# stm32c8t6.net
KiCad netlist of a schematic drawn in Altium Designer
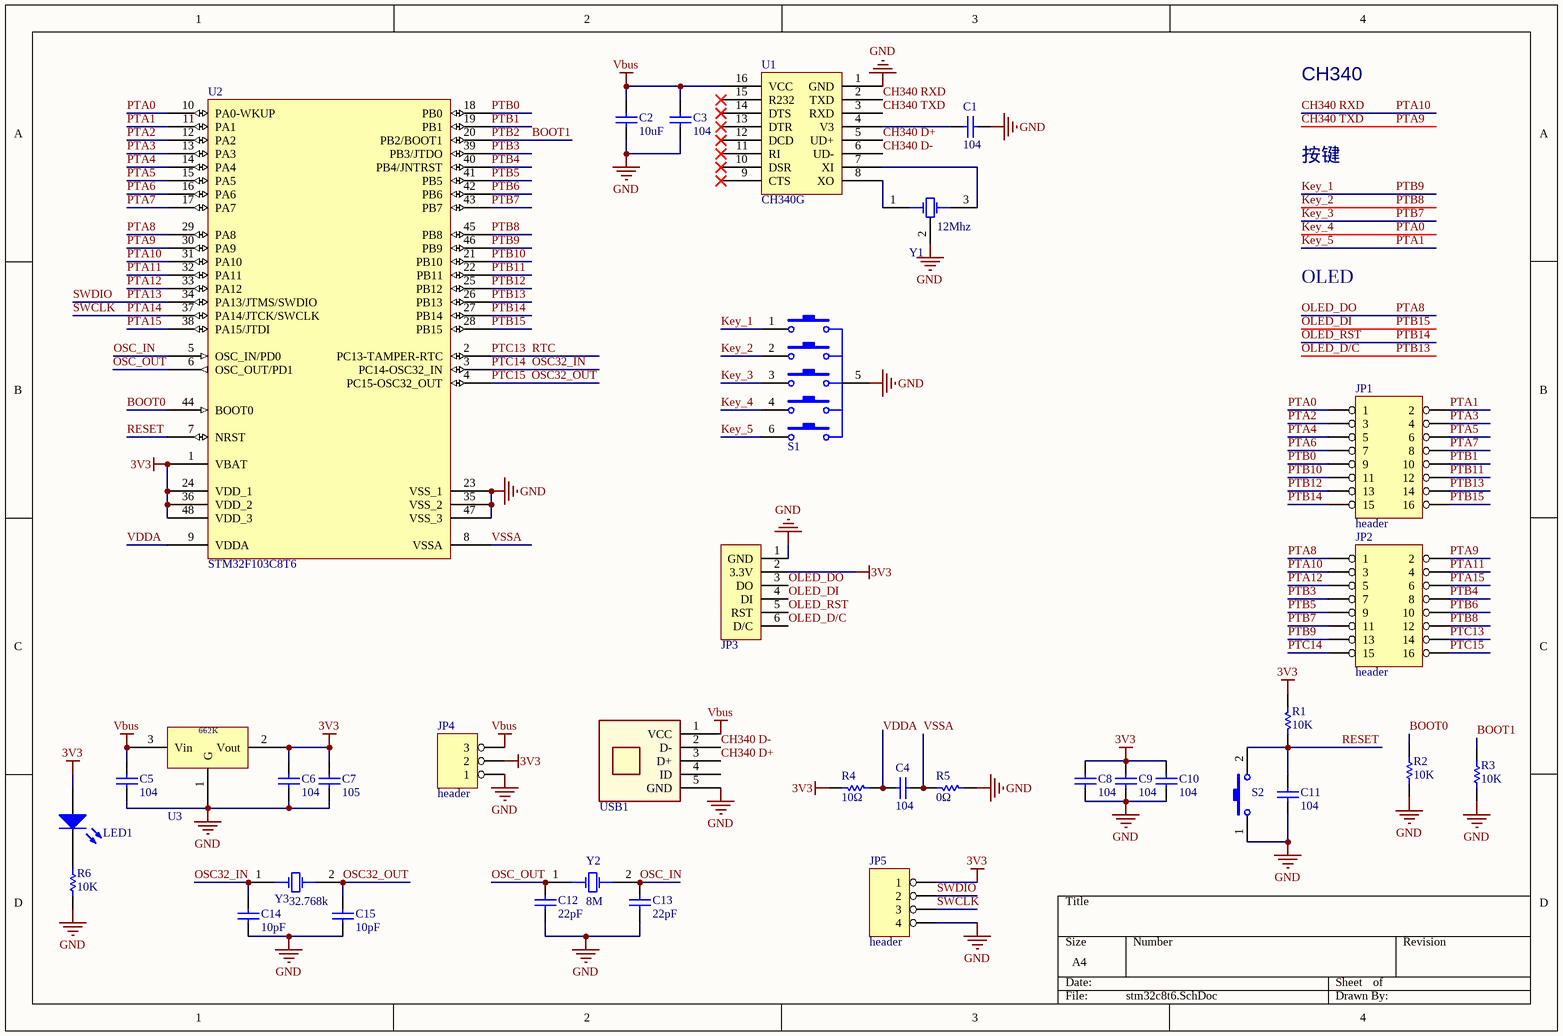
[diagram p0: stm32c8t6.SchDoc]

(export (version "E")
  (design (tool "Eeschema 10.0.6"))
  (components
    (comp (ref "C1")
      (value "104")
      (footprint "0603_C")
      (description "Capacitor")
      (fields (field (name "PUBLISHER") "Altium Limited"))
      (libsource (lib "My Footprint") (part "CAP"))
    )
    (comp (ref "C2")
      (value "10uF")
      (footprint "0805_c")
      (description "Capacitor")
      (fields (field (name "PUBLISHER") "Altium Limited"))
      (libsource (lib "My Footprint") (part "CAP"))
    )
    (comp (ref "C3")
      (value "104")
      (footprint "0603_C")
      (description "Capacitor")
      (fields (field (name "PUBLISHER") "Altium Limited"))
      (libsource (lib "My Footprint") (part "CAP"))
    )
    (comp (ref "C4")
      (value "104")
      (footprint "0603_C")
      (description "Capacitor")
      (fields (field (name "PUBLISHER") "Altium Limited"))
      (libsource (lib "My Footprint") (part "CAP"))
    )
    (comp (ref "C5")
      (value "104")
      (footprint "0603_C")
      (description "Capacitor")
      (fields (field (name "PUBLISHER") "Altium Limited"))
      (libsource (lib "My Footprint") (part "CAP"))
    )
    (comp (ref "C6")
      (value "104")
      (footprint "0603_C")
      (description "Capacitor")
      (fields (field (name "PUBLISHER") "Altium Limited"))
      (libsource (lib "My Footprint") (part "CAP"))
    )
    (comp (ref "C7")
      (value "105")
      (footprint "0805_c")
      (description "Capacitor")
      (fields (field (name "PUBLISHER") "Altium Limited"))
      (libsource (lib "My Footprint") (part "CAP"))
    )
    (comp (ref "C8")
      (value "104")
      (footprint "0603_C")
      (description "Capacitor")
      (fields (field (name "PUBLISHER") "Altium Limited"))
      (libsource (lib "My Footprint") (part "CAP"))
    )
    (comp (ref "C9")
      (value "104")
      (footprint "0603_C")
      (description "Capacitor")
      (fields (field (name "PUBLISHER") "Altium Limited"))
      (libsource (lib "My Footprint") (part "CAP"))
    )
    (comp (ref "C10")
      (value "104")
      (footprint "0603_C")
      (description "Capacitor")
      (fields (field (name "PUBLISHER") "Altium Limited"))
      (libsource (lib "My Footprint") (part "CAP"))
    )
    (comp (ref "C11")
      (value "104")
      (footprint "0603_C")
      (description "Capacitor")
      (fields (field (name "PUBLISHER") "Altium Limited"))
      (libsource (lib "My Footprint") (part "CAP"))
    )
    (comp (ref "C12")
      (value "22pF")
      (footprint "0603_C")
      (description "Capacitor")
      (fields (field (name "PUBLISHER") "Altium Limited"))
      (libsource (lib "My Footprint") (part "CAP"))
    )
    (comp (ref "C13")
      (value "22pF")
      (footprint "0603_C")
      (description "Capacitor")
      (fields (field (name "PUBLISHER") "Altium Limited"))
      (libsource (lib "My Footprint") (part "CAP"))
    )
    (comp (ref "C14")
      (value "10pF")
      (footprint "0603_C")
      (description "Capacitor")
      (fields (field (name "PUBLISHER") "Altium Limited"))
      (libsource (lib "My Footprint") (part "CAP"))
    )
    (comp (ref "C15")
      (value "10pF")
      (footprint "0603_C")
      (description "Capacitor")
      (fields (field (name "PUBLISHER") "Altium Limited"))
      (libsource (lib "My Footprint") (part "CAP"))
    )
    (comp (ref "JP1")
      (value "header")
      (footprint "header2X8")
      (libsource (lib "My Footprint") (part "HEADER 8X2"))
    )
    (comp (ref "JP2")
      (value "header")
      (footprint "header2X8")
      (libsource (lib "My Footprint") (part "HEADER 8X2"))
    )
    (comp (ref "JP3")
      (value "OLED 6Pin")
      (footprint "OLED_6Pin")
      (libsource (lib "My Library") (part "OLED 6Pin"))
    )
    (comp (ref "JP4")
      (value "header")
      (footprint "header3")
      (libsource (lib "My Footprint") (part "HEADER 3"))
    )
    (comp (ref "JP5")
      (value "header")
      (footprint "header4")
      (libsource (lib "My Footprint") (part "HEADER 4"))
    )
    (comp (ref "LED1")
      (value "LED Chip")
      (footprint "CLED1608-0603")
      (description "Typical Chip LED")
      (fields (field (name "PUBLISHER") "Altium Limited"))
      (libsource (lib "LisieLib_Ultimate") (part "LED Chip"))
    )
    (comp (ref "R1")
      (value "10K")
      (footprint "0603_R")
      (description "Resistor")
      (fields (field (name "PUBLISHER") "Altium Limited"))
      (libsource (lib "My Footprint") (part "RES"))
    )
    (comp (ref "R2")
      (value "10K")
      (footprint "0603_R")
      (description "Resistor")
      (fields (field (name "PUBLISHER") "Altium Limited"))
      (libsource (lib "My Footprint") (part "RES"))
    )
    (comp (ref "R3")
      (value "10K")
      (footprint "0603_R")
      (description "Resistor")
      (fields (field (name "PUBLISHER") "Altium Limited"))
      (libsource (lib "My Footprint") (part "RES"))
    )
    (comp (ref "R4")
      (value "10Ω")
      (footprint "0603_R")
      (description "Resistor")
      (fields (field (name "PUBLISHER") "Altium Limited"))
      (libsource (lib "My Footprint") (part "RES"))
    )
    (comp (ref "R5")
      (value "0Ω")
      (footprint "0603_R")
      (description "Resistor")
      (fields (field (name "PUBLISHER") "Altium Limited"))
      (libsource (lib "My Footprint") (part "RES"))
    )
    (comp (ref "R6")
      (value "10K")
      (footprint "0603_R")
      (description "Resistor")
      (fields (field (name "PUBLISHER") "Altium Limited"))
      (libsource (lib "My Footprint") (part "RES"))
    )
    (comp (ref "S1")
      (value "5 way switch")
      (footprint "5 way switch")
      (libsource (lib "My Library") (part "5 way switch"))
    )
    (comp (ref "S2") (value "Key") (footprint "SWITCH 4*4") (libsource (lib "My Library") (part "Key")))
    (comp (ref "U1")
      (value "CH340G")
      (footprint "SOIC-16")
      (description "SOIC")
      (libsource (lib "My Footprint") (part "CH340G"))
    )
    (comp (ref "U2")
      (value "STM32F103C8T6")
      (footprint "LQFP48")
      (description "STM32 ARM-based 32-bit MCU with 64 Kbytes Flash, 48-pin LQFP, Industrial Temperature")
      (fields (field (name "PUBLISHER") "Altium Limited"))
      (libsource (lib "My Footprint") (part "STM32F103C8T6"))
    )
    (comp (ref "U3")
      (value "XC6206P332MR")
      (footprint "SOT95P280X120-3N")
      (libsource (lib "My Library") (part "XC6206P332MR"))
    )
    (comp (ref "USB1")
      (value "USB_Mini")
      (footprint "USB_Mini2")
      (libsource (lib "My Library") (part "USB_Mini"))
    )
    (comp (ref "Y1")
      (value "XTAL 8Mhz 3215 3pin")
      (footprint "3213 3Pin")
      (fields (field (name "ALTIUM_UNNAMED_1") "12Mhz"))
      (libsource (lib "My Library") (part "XTAL 8Mhz 3215 3pin"))
    )
    (comp (ref "Y2")
      (value "8M")
      (footprint "5032 2Pin")
      (libsource (lib "My Library") (part "XTAL 8Mhz 2pin"))
    )
    (comp (ref "Y3")
      (value "XTAL 32.768KHz 2P")
      (footprint "3215 2Pin")
      (fields (field (name "ALTIUM_UNNAMED_1") "32.768k"))
      (libsource (lib "My Library") (part "XTAL 32.768KHz 2P"))
    )
  )
  (nets
    (net (code "1") (name "/BOOT0") (class "Default")
      (node (ref "R2") (pin "2") (pinfunction "2_2") (pintype "passive"))
      (node (ref "U2") (pin "44") (pinfunction "BOOT0_44") (pintype "input"))
    )
    (net (code "2") (name "/BOOT1") (class "Default")
      (node (ref "R3") (pin "2") (pinfunction "2_2") (pintype "passive"))
      (node (ref "U2") (pin "20") (pinfunction "PB2/BOOT1_20") (pintype "bidirectional"))
    )
    (net (code "3") (name "/CH340 D+") (class "Default")
      (node (ref "U1") (pin "5") (pinfunction "UD+_5") (pintype "passive"))
      (node (ref "USB1") (pin "3") (pinfunction "D+_3") (pintype "passive"))
    )
    (net (code "4") (name "/CH340 D-") (class "Default")
      (node (ref "U1") (pin "6") (pinfunction "UD-_6") (pintype "passive"))
      (node (ref "USB1") (pin "2") (pinfunction "D-_2") (pintype "passive"))
    )
    (net (code "5") (name "/CH340 RXD") (class "Default")
      (node (ref "JP2") (pin "3") (pinfunction "3_3") (pintype "passive"))
      (node (ref "U1") (pin "2") (pinfunction "TXD_2") (pintype "passive"))
      (node (ref "U2") (pin "31") (pinfunction "PA10_31") (pintype "bidirectional"))
    )
    (net (code "6") (name "/CH340 TXD") (class "Default")
      (node (ref "JP2") (pin "2") (pinfunction "2_2") (pintype "passive"))
      (node (ref "U1") (pin "3") (pinfunction "RXD_3") (pintype "passive"))
      (node (ref "U2") (pin "30") (pinfunction "PA9_30") (pintype "bidirectional"))
    )
    (net (code "7") (name "/Key_1") (class "Default")
      (node (ref "JP2") (pin "13") (pinfunction "13_13") (pintype "passive"))
      (node (ref "S1") (pin "1") (pinfunction "1_1") (pintype "passive"))
      (node (ref "U2") (pin "46") (pinfunction "PB9_46") (pintype "bidirectional"))
    )
    (net (code "8") (name "/Key_2") (class "Default")
      (node (ref "JP2") (pin "12") (pinfunction "12_12") (pintype "passive"))
      (node (ref "S1") (pin "2") (pinfunction "1_2") (pintype "passive"))
      (node (ref "U2") (pin "45") (pinfunction "PB8_45") (pintype "bidirectional"))
    )
    (net (code "9") (name "/Key_3") (class "Default")
      (node (ref "JP2") (pin "11") (pinfunction "11_11") (pintype "passive"))
      (node (ref "S1") (pin "3") (pinfunction "1_3") (pintype "passive"))
      (node (ref "U2") (pin "43") (pinfunction "PB7_43") (pintype "bidirectional"))
    )
    (net (code "10") (name "/Key_4") (class "Default")
      (node (ref "JP1") (pin "1") (pinfunction "1_1") (pintype "passive"))
      (node (ref "S1") (pin "4") (pinfunction "1_4") (pintype "passive"))
      (node (ref "U2") (pin "10") (pinfunction "PA0-WKUP_10") (pintype "bidirectional"))
    )
    (net (code "11") (name "/Key_5") (class "Default")
      (node (ref "JP1") (pin "2") (pinfunction "2_2") (pintype "passive"))
      (node (ref "S1") (pin "6") (pinfunction "1_6") (pintype "passive"))
      (node (ref "U2") (pin "11") (pinfunction "PA1_11") (pintype "bidirectional"))
    )
    (net (code "12") (name "/OLED_DI") (class "Default")
      (node (ref "JP1") (pin "16") (pinfunction "16_16") (pintype "passive"))
      (node (ref "JP3") (pin "4") (pinfunction "DI_4") (pintype "passive"))
      (node (ref "U2") (pin "28") (pinfunction "PB15_28") (pintype "bidirectional"))
    )
    (net (code "13") (name "/OLED_DO") (class "Default")
      (node (ref "JP2") (pin "1") (pinfunction "1_1") (pintype "passive"))
      (node (ref "JP3") (pin "3") (pinfunction "DO_3") (pintype "passive"))
      (node (ref "U2") (pin "29") (pinfunction "PA8_29") (pintype "bidirectional"))
    )
    (net (code "14") (name "/OLED_D{slash}C") (class "Default")
      (node (ref "JP1") (pin "14") (pinfunction "14_14") (pintype "passive"))
      (node (ref "JP3") (pin "6") (pinfunction "D/C_6") (pintype "passive"))
      (node (ref "U2") (pin "26") (pinfunction "PB13_26") (pintype "bidirectional"))
    )
    (net (code "15") (name "/OLED_RST") (class "Default")
      (node (ref "JP1") (pin "15") (pinfunction "15_15") (pintype "passive"))
      (node (ref "JP3") (pin "5") (pinfunction "RST_5") (pintype "passive"))
      (node (ref "U2") (pin "27") (pinfunction "PB14_27") (pintype "bidirectional"))
    )
    (net (code "16") (name "/OSC32_IN") (class "Default")
      (node (ref "C14") (pin "2") (pinfunction "2_2") (pintype "passive"))
      (node (ref "JP2") (pin "15") (pinfunction "15_15") (pintype "passive"))
      (node (ref "U2") (pin "3") (pinfunction "PC14-OSC32_IN_3") (pintype "bidirectional"))
      (node (ref "Y3") (pin "1") (pinfunction "OSC1_1") (pintype "passive"))
    )
    (net (code "17") (name "/OSC32_OUT") (class "Default")
      (node (ref "C15") (pin "2") (pinfunction "2_2") (pintype "passive"))
      (node (ref "JP2") (pin "16") (pinfunction "16_16") (pintype "passive"))
      (node (ref "U2") (pin "4") (pinfunction "PC15-OSC32_OUT_4") (pintype "bidirectional"))
      (node (ref "Y3") (pin "2") (pinfunction "OSC2_2") (pintype "passive"))
    )
    (net (code "18") (name "/OSC_IN") (class "Default")
      (node (ref "C13") (pin "2") (pinfunction "2_2") (pintype "passive"))
      (node (ref "U2") (pin "5") (pinfunction "OSC_IN/PD0_5") (pintype "input"))
      (node (ref "Y2") (pin "2") (pinfunction "OSC2_2") (pintype "passive"))
    )
    (net (code "19") (name "/OSC_OUT") (class "Default")
      (node (ref "C12") (pin "2") (pinfunction "2_2") (pintype "passive"))
      (node (ref "U2") (pin "6") (pinfunction "OSC_OUT/PD1_6") (pintype "output"))
      (node (ref "Y2") (pin "1") (pinfunction "OSC1_1") (pintype "passive"))
    )
    (net (code "20") (name "/PTA2") (class "Default")
      (node (ref "JP1") (pin "3") (pinfunction "3_3") (pintype "passive"))
      (node (ref "U2") (pin "12") (pinfunction "PA2_12") (pintype "bidirectional"))
    )
    (net (code "21") (name "/PTA3") (class "Default")
      (node (ref "JP1") (pin "4") (pinfunction "4_4") (pintype "passive"))
      (node (ref "U2") (pin "13") (pinfunction "PA3_13") (pintype "bidirectional"))
    )
    (net (code "22") (name "/PTA4") (class "Default")
      (node (ref "JP1") (pin "5") (pinfunction "5_5") (pintype "passive"))
      (node (ref "U2") (pin "14") (pinfunction "PA4_14") (pintype "bidirectional"))
    )
    (net (code "23") (name "/PTA5") (class "Default")
      (node (ref "JP1") (pin "6") (pinfunction "6_6") (pintype "passive"))
      (node (ref "U2") (pin "15") (pinfunction "PA5_15") (pintype "bidirectional"))
    )
    (net (code "24") (name "/PTA6") (class "Default")
      (node (ref "JP1") (pin "7") (pinfunction "7_7") (pintype "passive"))
      (node (ref "U2") (pin "16") (pinfunction "PA6_16") (pintype "bidirectional"))
    )
    (net (code "25") (name "/PTA7") (class "Default")
      (node (ref "JP1") (pin "8") (pinfunction "8_8") (pintype "passive"))
      (node (ref "U2") (pin "17") (pinfunction "PA7_17") (pintype "bidirectional"))
    )
    (net (code "26") (name "/PTA11") (class "Default")
      (node (ref "JP2") (pin "4") (pinfunction "4_4") (pintype "passive"))
      (node (ref "U2") (pin "32") (pinfunction "PA11_32") (pintype "bidirectional"))
    )
    (net (code "27") (name "/PTA12") (class "Default")
      (node (ref "JP2") (pin "5") (pinfunction "5_5") (pintype "passive"))
      (node (ref "U2") (pin "33") (pinfunction "PA12_33") (pintype "bidirectional"))
    )
    (net (code "28") (name "/PTA13") (class "Default")
      (node (ref "JP5") (pin "2") (pinfunction "2_2") (pintype "passive"))
      (node (ref "U2") (pin "34") (pinfunction "PA13/JTMS/SWDIO_34") (pintype "bidirectional"))
    )
    (net (code "29") (name "/PTA14") (class "Default")
      (node (ref "JP5") (pin "3") (pinfunction "3_3") (pintype "passive"))
      (node (ref "U2") (pin "37") (pinfunction "PA14/JTCK/SWCLK_37") (pintype "bidirectional"))
    )
    (net (code "30") (name "/PTA15") (class "Default")
      (node (ref "JP2") (pin "6") (pinfunction "6_6") (pintype "passive"))
      (node (ref "U2") (pin "38") (pinfunction "PA15/JTDI_38") (pintype "bidirectional"))
    )
    (net (code "31") (name "/PTB0") (class "Default")
      (node (ref "JP1") (pin "9") (pinfunction "9_9") (pintype "passive"))
      (node (ref "U2") (pin "18") (pinfunction "PB0_18") (pintype "bidirectional"))
    )
    (net (code "32") (name "/PTB1") (class "Default")
      (node (ref "JP1") (pin "10") (pinfunction "10_10") (pintype "passive"))
      (node (ref "U2") (pin "19") (pinfunction "PB1_19") (pintype "bidirectional"))
    )
    (net (code "33") (name "/PTB3") (class "Default")
      (node (ref "JP2") (pin "7") (pinfunction "7_7") (pintype "passive"))
      (node (ref "U2") (pin "39") (pinfunction "PB3/JTDO_39") (pintype "bidirectional"))
    )
    (net (code "34") (name "/PTB4") (class "Default")
      (node (ref "JP2") (pin "8") (pinfunction "8_8") (pintype "passive"))
      (node (ref "U2") (pin "40") (pinfunction "PB4/JNTRST_40") (pintype "bidirectional"))
    )
    (net (code "35") (name "/PTB5") (class "Default")
      (node (ref "JP2") (pin "9") (pinfunction "9_9") (pintype "passive"))
      (node (ref "U2") (pin "41") (pinfunction "PB5_41") (pintype "bidirectional"))
    )
    (net (code "36") (name "/PTB6") (class "Default")
      (node (ref "JP2") (pin "10") (pinfunction "10_10") (pintype "passive"))
      (node (ref "U2") (pin "42") (pinfunction "PB6_42") (pintype "bidirectional"))
    )
    (net (code "37") (name "/PTB10") (class "Default")
      (node (ref "JP1") (pin "11") (pinfunction "11_11") (pintype "passive"))
      (node (ref "U2") (pin "21") (pinfunction "PB10_21") (pintype "bidirectional"))
    )
    (net (code "38") (name "/PTB11") (class "Default")
      (node (ref "JP1") (pin "12") (pinfunction "12_12") (pintype "passive"))
      (node (ref "U2") (pin "22") (pinfunction "PB11_22") (pintype "bidirectional"))
    )
    (net (code "39") (name "/PTB12") (class "Default")
      (node (ref "JP1") (pin "13") (pinfunction "13_13") (pintype "passive"))
      (node (ref "U2") (pin "25") (pinfunction "PB12_25") (pintype "bidirectional"))
    )
    (net (code "40") (name "/PTC13") (class "Default")
      (node (ref "JP2") (pin "14") (pinfunction "14_14") (pintype "passive"))
      (node (ref "U2") (pin "2") (pinfunction "PC13-TAMPER-RTC_2") (pintype "bidirectional"))
    )
    (net (code "41") (name "/RESET") (class "Default")
      (node (ref "C11") (pin "2") (pinfunction "2_2") (pintype "passive"))
      (node (ref "R1") (pin "2") (pinfunction "2_2") (pintype "passive"))
      (node (ref "S2") (pin "2") (pinfunction "2_2") (pintype "passive"))
      (node (ref "U2") (pin "7") (pinfunction "NRST_7") (pintype "bidirectional"))
    )
    (net (code "42") (name "/VDDA") (class "Default")
      (node (ref "C4") (pin "2") (pinfunction "2_2") (pintype "passive"))
      (node (ref "R4") (pin "2") (pinfunction "2_2") (pintype "passive"))
      (node (ref "U2") (pin "9") (pinfunction "VDDA_9") (pintype "power_in"))
    )
    (net (code "43") (name "/VSSA") (class "Default")
      (node (ref "C4") (pin "1") (pinfunction "1_1") (pintype "passive"))
      (node (ref "R5") (pin "1") (pinfunction "1_1") (pintype "passive"))
      (node (ref "U2") (pin "8") (pinfunction "VSSA_8") (pintype "power_in"))
    )
    (net (code "44") (name "3V3") (class "Default")
      (node (ref "C10") (pin "2") (pinfunction "2_2") (pintype "passive"))
      (node (ref "C6") (pin "2") (pinfunction "2_2") (pintype "passive"))
      (node (ref "C7") (pin "2") (pinfunction "2_2") (pintype "passive"))
      (node (ref "C8") (pin "2") (pinfunction "2_2") (pintype "passive"))
      (node (ref "C9") (pin "2") (pinfunction "2_2") (pintype "passive"))
      (node (ref "JP3") (pin "2") (pinfunction "3.3V_2") (pintype "passive"))
      (node (ref "JP4") (pin "2") (pinfunction "2_2") (pintype "passive"))
      (node (ref "JP5") (pin "1") (pinfunction "1_1") (pintype "passive"))
      (node (ref "LED1") (pin "1") (pinfunction "A_1") (pintype "passive"))
      (node (ref "R1") (pin "1") (pinfunction "1_1") (pintype "passive"))
      (node (ref "R4") (pin "1") (pinfunction "1_1") (pintype "passive"))
      (node (ref "U2") (pin "1") (pinfunction "VBAT_1") (pintype "power_in"))
      (node (ref "U2") (pin "24") (pinfunction "VDD_1_24") (pintype "power_in"))
      (node (ref "U2") (pin "36") (pinfunction "VDD_2_36") (pintype "power_in"))
      (node (ref "U2") (pin "48") (pinfunction "VDD_3_48") (pintype "power_in"))
      (node (ref "U3") (pin "2") (pinfunction "Vout_2") (pintype "power_in"))
    )
    (net (code "45") (name "GND") (class "Default")
      (node (ref "C1") (pin "1") (pinfunction "1_1") (pintype "passive"))
      (node (ref "C10") (pin "1") (pinfunction "1_1") (pintype "passive"))
      (node (ref "C11") (pin "1") (pinfunction "1_1") (pintype "passive"))
      (node (ref "C12") (pin "1") (pinfunction "1_1") (pintype "passive"))
      (node (ref "C13") (pin "1") (pinfunction "1_1") (pintype "passive"))
      (node (ref "C14") (pin "1") (pinfunction "1_1") (pintype "passive"))
      (node (ref "C15") (pin "1") (pinfunction "1_1") (pintype "passive"))
      (node (ref "C2") (pin "1") (pinfunction "1_1") (pintype "passive"))
      (node (ref "C3") (pin "2") (pinfunction "2_2") (pintype "passive"))
      (node (ref "C5") (pin "1") (pinfunction "1_1") (pintype "passive"))
      (node (ref "C6") (pin "1") (pinfunction "1_1") (pintype "passive"))
      (node (ref "C7") (pin "1") (pinfunction "1_1") (pintype "passive"))
      (node (ref "C8") (pin "1") (pinfunction "1_1") (pintype "passive"))
      (node (ref "C9") (pin "1") (pinfunction "1_1") (pintype "passive"))
      (node (ref "JP3") (pin "1") (pinfunction "GND_1") (pintype "passive"))
      (node (ref "JP4") (pin "1") (pinfunction "1_1") (pintype "passive"))
      (node (ref "JP5") (pin "4") (pinfunction "4_4") (pintype "passive"))
      (node (ref "R2") (pin "1") (pinfunction "1_1") (pintype "passive"))
      (node (ref "R3") (pin "1") (pinfunction "1_1") (pintype "passive"))
      (node (ref "R5") (pin "2") (pinfunction "2_2") (pintype "passive"))
      (node (ref "R6") (pin "1") (pinfunction "1_1") (pintype "passive"))
      (node (ref "S1") (pin "5") (pinfunction "1_5") (pintype "passive"))
      (node (ref "S2") (pin "1") (pinfunction "1_1") (pintype "passive"))
      (node (ref "U1") (pin "1") (pinfunction "GND_1") (pintype "passive"))
      (node (ref "U2") (pin "23") (pinfunction "VSS_1_23") (pintype "power_in"))
      (node (ref "U2") (pin "35") (pinfunction "VSS_2_35") (pintype "power_in"))
      (node (ref "U2") (pin "47") (pinfunction "VSS_3_47") (pintype "power_in"))
      (node (ref "U3") (pin "1") (pinfunction "G_1") (pintype "power_in"))
      (node (ref "USB1") (pin "5") (pinfunction "GND_5") (pintype "passive"))
      (node (ref "Y1") (pin "2") (pinfunction "OSC2_2") (pintype "passive"))
    )
    (net (code "46") (name "Net-(LED1-K)") (class "Default")
      (node (ref "LED1") (pin "2") (pinfunction "K_2") (pintype "passive"))
      (node (ref "R6") (pin "2") (pinfunction "2_2") (pintype "passive"))
    )
    (net (code "47") (name "Net-(U1-V3)") (class "Default")
      (node (ref "C1") (pin "2") (pinfunction "2_2") (pintype "passive"))
      (node (ref "U1") (pin "4") (pinfunction "V3_4") (pintype "passive"))
    )
    (net (code "48") (name "Net-(U1-XI)") (class "Default")
      (node (ref "U1") (pin "7") (pinfunction "XI_7") (pintype "passive"))
      (node (ref "Y1") (pin "3") (pinfunction "OSC1_3") (pintype "passive"))
    )
    (net (code "49") (name "Net-(U1-XO)") (class "Default")
      (node (ref "U1") (pin "8") (pinfunction "XO_8") (pintype "passive"))
      (node (ref "Y1") (pin "1") (pinfunction "OSC1_1") (pintype "passive"))
    )
    (net (code "50") (name "Vbus") (class "Default")
      (node (ref "C2") (pin "2") (pinfunction "2_2") (pintype "passive"))
      (node (ref "C3") (pin "1") (pinfunction "1_1") (pintype "passive"))
      (node (ref "C5") (pin "2") (pinfunction "2_2") (pintype "passive"))
      (node (ref "JP4") (pin "3") (pinfunction "3_3") (pintype "passive"))
      (node (ref "U1") (pin "16") (pinfunction "VCC_16") (pintype "passive"))
      (node (ref "U3") (pin "3") (pinfunction "Vin_3") (pintype "power_in"))
      (node (ref "USB1") (pin "1") (pinfunction "VCC_1") (pintype "passive"))
    )
    (net (code "51") (name "unconnected-(U1-CTS-Pad9)") (class "Default")
      (node (ref "U1") (pin "9") (pinfunction "CTS_9") (pintype "passive+no_connect"))
    )
    (net (code "52") (name "unconnected-(U1-DCD-Pad12)") (class "Default")
      (node (ref "U1") (pin "12") (pinfunction "DCD_12") (pintype "passive+no_connect"))
    )
    (net (code "53") (name "unconnected-(U1-DSR-Pad10)") (class "Default")
      (node (ref "U1") (pin "10") (pinfunction "DSR_10") (pintype "passive+no_connect"))
    )
    (net (code "54") (name "unconnected-(U1-DTR-Pad13)") (class "Default")
      (node (ref "U1") (pin "13") (pinfunction "DTR_13") (pintype "passive+no_connect"))
    )
    (net (code "55") (name "unconnected-(U1-DTS-Pad14)") (class "Default")
      (node (ref "U1") (pin "14") (pinfunction "DTS_14") (pintype "passive+no_connect"))
    )
    (net (code "56") (name "unconnected-(U1-R232-Pad15)") (class "Default")
      (node (ref "U1") (pin "15") (pinfunction "R232_15") (pintype "passive+no_connect"))
    )
    (net (code "57") (name "unconnected-(U1-RI-Pad11)") (class "Default")
      (node (ref "U1") (pin "11") (pinfunction "RI_11") (pintype "passive+no_connect"))
    )
    (net (code "58") (name "unconnected-(USB1-ID-Pad4)") (class "Default")
      (node (ref "USB1") (pin "4") (pinfunction "ID_4") (pintype "passive"))
    )
  )
)
